# S14FullAmpV2.net
KiCad netlist of a schematic drawn in EAGLE
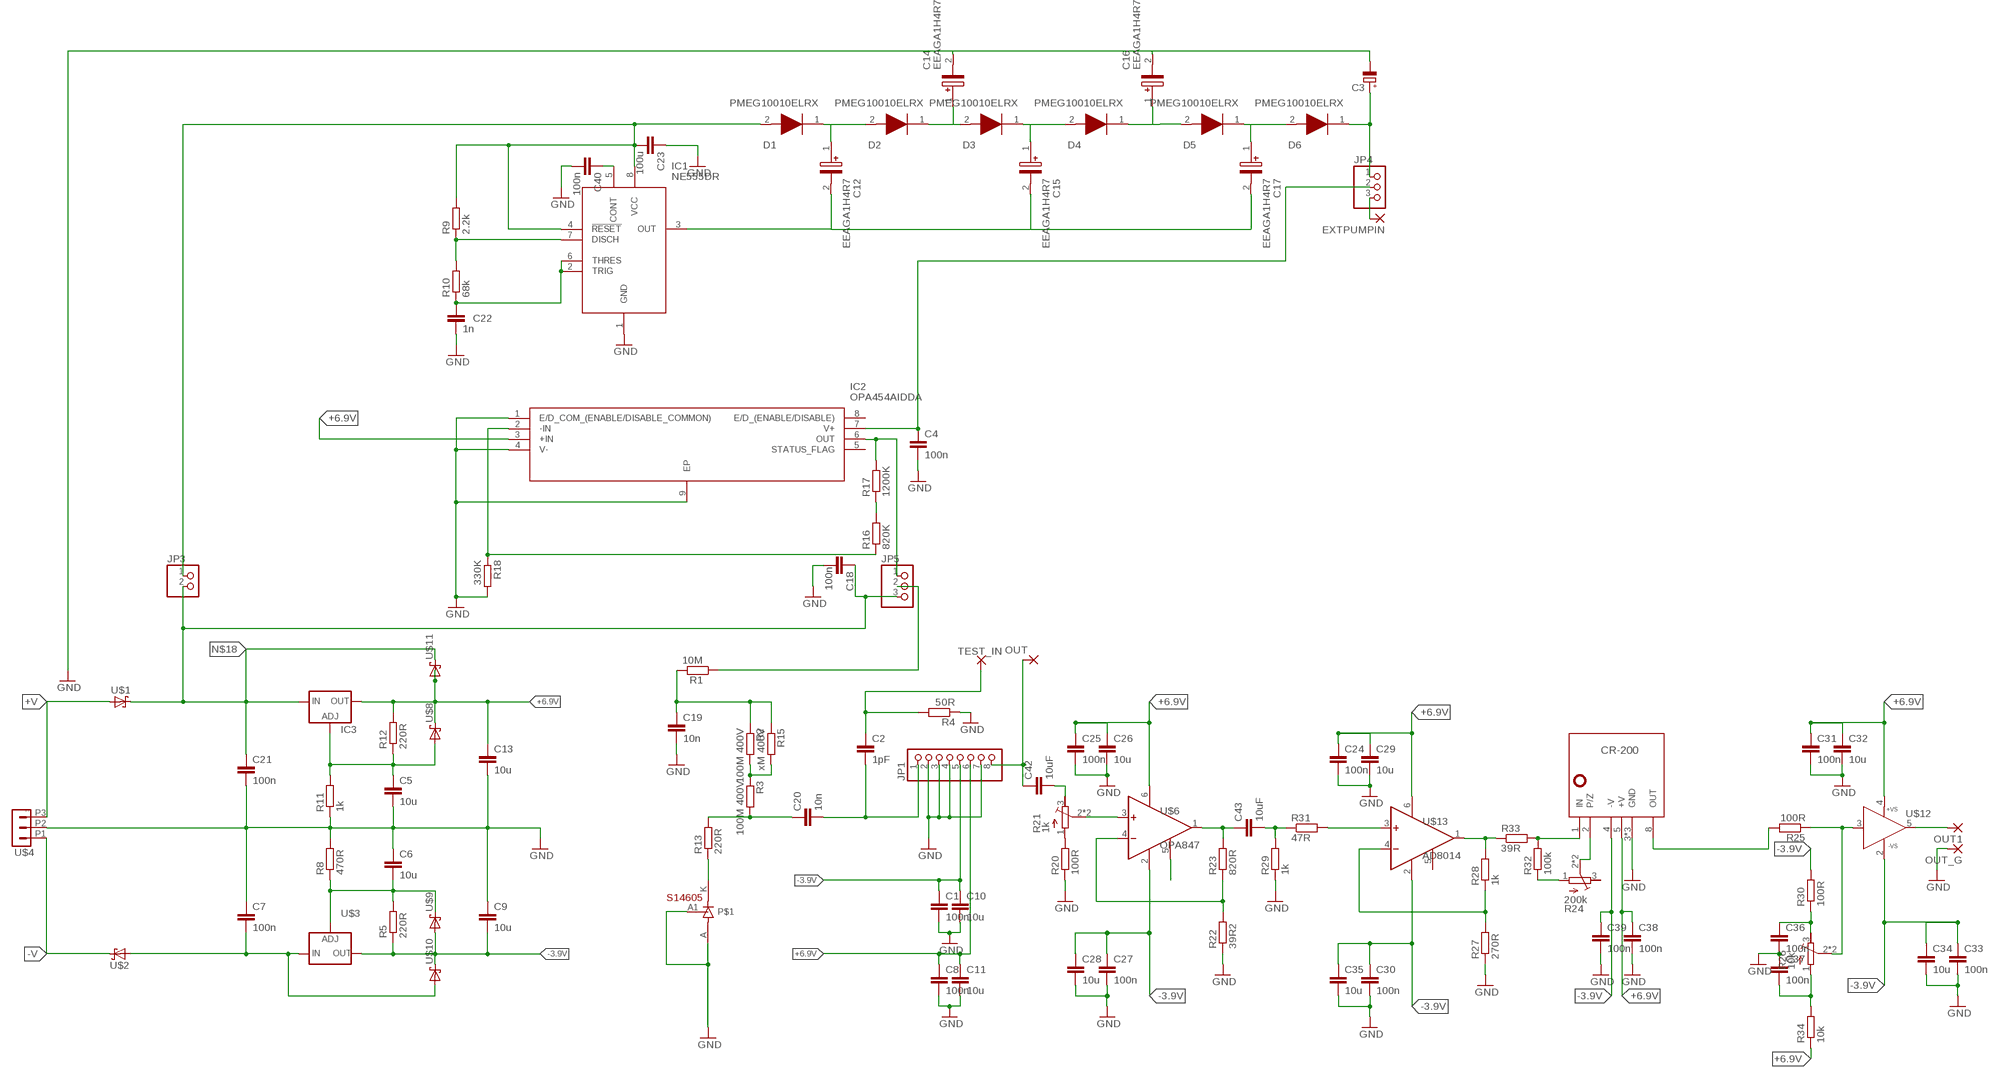
[diagram p0: schematic, sheet 1]

(export (version "E")
  (design (tool "Eeschema 10.0.6"))
  (components
    (comp (ref "C1")
      (value "100n")
      (footprint "eagle-import:C0603")
      (libsource (lib "eagle-import") (part "resistor_C-EUC0603"))
    )
    (comp (ref "C2")
      (value "1pF")
      (footprint "eagle-import:C0603")
      (libsource (lib "eagle-import") (part "C-EUC0603"))
    )
    (comp (ref "C3")
      (value "CPOL-EUE3.5-8")
      (footprint "eagle-import:E3,5-8")
      (libsource (lib "eagle-import") (part "CPOL-EUE3.5-8"))
    )
    (comp (ref "C4")
      (value "100n")
      (footprint "eagle-import:C0603")
      (libsource (lib "eagle-import") (part "resistor_C-EUC0603"))
    )
    (comp (ref "C5")
      (value "10u")
      (footprint "eagle-import:C0805")
      (libsource (lib "eagle-import") (part "C-EUC0805"))
    )
    (comp (ref "C6")
      (value "10u")
      (footprint "eagle-import:C0805")
      (libsource (lib "eagle-import") (part "C-EUC0805"))
    )
    (comp (ref "C7")
      (value "100n")
      (footprint "eagle-import:C0603")
      (libsource (lib "eagle-import") (part "C-EUC0603"))
    )
    (comp (ref "C8")
      (value "100n")
      (footprint "eagle-import:C0603")
      (libsource (lib "eagle-import") (part "resistor_C-EUC0603"))
    )
    (comp (ref "C9")
      (value "10u")
      (footprint "eagle-import:C0805")
      (libsource (lib "eagle-import") (part "C-EUC0805"))
    )
    (comp (ref "C10")
      (value "10u")
      (footprint "eagle-import:C0805")
      (libsource (lib "eagle-import") (part "resistor_C-EUC0805"))
    )
    (comp (ref "C11")
      (value "10u")
      (footprint "eagle-import:C0805")
      (libsource (lib "eagle-import") (part "resistor_C-EUC0805"))
    )
    (comp (ref "C12")
      (value "EEAGA1H4R7")
      (footprint "eagle-import:CAPPRD150W50D400H800")
      (libsource (lib "eagle-import") (part "EEAGA1H4R7"))
    )
    (comp (ref "C13")
      (value "10u")
      (footprint "eagle-import:C0805")
      (libsource (lib "eagle-import") (part "C-EUC0805"))
    )
    (comp (ref "C14")
      (value "EEAGA1H4R7")
      (footprint "eagle-import:CAPPRD150W50D400H800")
      (libsource (lib "eagle-import") (part "EEAGA1H4R7"))
    )
    (comp (ref "C15")
      (value "EEAGA1H4R7")
      (footprint "eagle-import:CAPPRD150W50D400H800")
      (libsource (lib "eagle-import") (part "EEAGA1H4R7"))
    )
    (comp (ref "C16")
      (value "EEAGA1H4R7")
      (footprint "eagle-import:CAPPRD150W50D400H800")
      (libsource (lib "eagle-import") (part "EEAGA1H4R7"))
    )
    (comp (ref "C17")
      (value "EEAGA1H4R7")
      (footprint "eagle-import:CAPPRD150W50D400H800")
      (libsource (lib "eagle-import") (part "EEAGA1H4R7"))
    )
    (comp (ref "C18")
      (value "100n")
      (footprint "eagle-import:C0603")
      (libsource (lib "eagle-import") (part "C-EUC0603"))
    )
    (comp (ref "C19")
      (value "10n")
      (footprint "eagle-import:C0603")
      (libsource (lib "eagle-import") (part "resistor_C-EUC0603"))
    )
    (comp (ref "C20")
      (value "10n")
      (footprint "eagle-import:C0603")
      (libsource (lib "eagle-import") (part "resistor_C-EUC0603"))
    )
    (comp (ref "C21")
      (value "100n")
      (footprint "eagle-import:C0603")
      (libsource (lib "eagle-import") (part "C-EUC0603"))
    )
    (comp (ref "C22")
      (value "1n")
      (footprint "eagle-import:C0603")
      (libsource (lib "eagle-import") (part "resistor_C-EUC0603"))
    )
    (comp (ref "C23")
      (value "100u")
      (footprint "eagle-import:C0603")
      (libsource (lib "eagle-import") (part "C-EUC0603"))
    )
    (comp (ref "C24")
      (value "100n")
      (footprint "eagle-import:C0603")
      (libsource (lib "eagle-import") (part "C-EUC0603"))
    )
    (comp (ref "C25")
      (value "100n")
      (footprint "eagle-import:C0603")
      (libsource (lib "eagle-import") (part "C-EUC0603"))
    )
    (comp (ref "C26")
      (value "10u")
      (footprint "eagle-import:C0805")
      (libsource (lib "eagle-import") (part "resistor_C-EUC0805"))
    )
    (comp (ref "C27")
      (value "100n")
      (footprint "eagle-import:C0603")
      (libsource (lib "eagle-import") (part "C-EUC0603"))
    )
    (comp (ref "C28")
      (value "10u")
      (footprint "eagle-import:C0805")
      (libsource (lib "eagle-import") (part "resistor_C-EUC0805"))
    )
    (comp (ref "C29")
      (value "10u")
      (footprint "eagle-import:C0805")
      (libsource (lib "eagle-import") (part "resistor_C-EUC0805"))
    )
    (comp (ref "C30")
      (value "100n")
      (footprint "eagle-import:C0603")
      (libsource (lib "eagle-import") (part "C-EUC0603"))
    )
    (comp (ref "C31")
      (value "100n")
      (footprint "eagle-import:C0603")
      (libsource (lib "eagle-import") (part "C-EUC0603"))
    )
    (comp (ref "C32")
      (value "10u")
      (footprint "eagle-import:C0805")
      (libsource (lib "eagle-import") (part "resistor_C-EUC0805"))
    )
    (comp (ref "C33")
      (value "100n")
      (footprint "eagle-import:C0603")
      (libsource (lib "eagle-import") (part "C-EUC0603"))
    )
    (comp (ref "C34")
      (value "10u")
      (footprint "eagle-import:C0805")
      (libsource (lib "eagle-import") (part "resistor_C-EUC0805"))
    )
    (comp (ref "C35")
      (value "10u")
      (footprint "eagle-import:C0805")
      (libsource (lib "eagle-import") (part "resistor_C-EUC0805"))
    )
    (comp (ref "C36")
      (value "100n")
      (footprint "eagle-import:C0603")
      (libsource (lib "eagle-import") (part "C-EUC0603"))
    )
    (comp (ref "C37")
      (value "100n")
      (footprint "eagle-import:C0603")
      (libsource (lib "eagle-import") (part "C-EUC0603"))
    )
    (comp (ref "C38")
      (value "100n")
      (footprint "eagle-import:C0603")
      (libsource (lib "eagle-import") (part "C-EUC0603"))
    )
    (comp (ref "C39")
      (value "100n")
      (footprint "eagle-import:C0603")
      (libsource (lib "eagle-import") (part "C-EUC0603"))
    )
    (comp (ref "C40")
      (value "100n")
      (footprint "eagle-import:C0603")
      (libsource (lib "eagle-import") (part "C-EUC0603"))
    )
    (comp (ref "C42")
      (value "10uF")
      (footprint "eagle-import:C0805")
      (libsource (lib "eagle-import") (part "resistor_348_C-EUC0805"))
    )
    (comp (ref "C43")
      (value "10uF")
      (footprint "eagle-import:C0805")
      (libsource (lib "eagle-import") (part "resistor_348_C-EUC0805"))
    )
    (comp (ref "CR-200")
      (value "CR-200H")
      (footprint "eagle-import:CR-XXX-H")
      (libsource (lib "eagle-import") (part "CR-200H"))
    )
    (comp (ref "D1")
      (value "PMEG10010ELRX")
      (footprint "eagle-import:SODFL3517X110N")
      (fields (field (name "MOUSER_PART_NUMBER") "771-PMEG10010ELRX"))
      (libsource (lib "eagle-import") (part "PMEG10010ELRX"))
    )
    (comp (ref "D2")
      (value "PMEG10010ELRX")
      (footprint "eagle-import:SODFL3517X110N")
      (fields (field (name "MOUSER_PART_NUMBER") "771-PMEG10010ELRX"))
      (libsource (lib "eagle-import") (part "PMEG10010ELRX"))
    )
    (comp (ref "D3")
      (value "PMEG10010ELRX")
      (footprint "eagle-import:SODFL3517X110N")
      (fields (field (name "MOUSER_PART_NUMBER") "771-PMEG10010ELRX"))
      (libsource (lib "eagle-import") (part "PMEG10010ELRX"))
    )
    (comp (ref "D4")
      (value "PMEG10010ELRX")
      (footprint "eagle-import:SODFL3517X110N")
      (fields (field (name "MOUSER_PART_NUMBER") "771-PMEG10010ELRX"))
      (libsource (lib "eagle-import") (part "PMEG10010ELRX"))
    )
    (comp (ref "D5")
      (value "PMEG10010ELRX")
      (footprint "eagle-import:SODFL3517X110N")
      (fields (field (name "MOUSER_PART_NUMBER") "771-PMEG10010ELRX"))
      (libsource (lib "eagle-import") (part "PMEG10010ELRX"))
    )
    (comp (ref "D6")
      (value "PMEG10010ELRX")
      (footprint "eagle-import:SODFL3517X110N")
      (fields (field (name "MOUSER_PART_NUMBER") "771-PMEG10010ELRX"))
      (libsource (lib "eagle-import") (part "PMEG10010ELRX"))
    )
    (comp (ref "EXTPUMPIN")
      (value "1,6/0,9")
      (footprint "eagle-import:1,6_0,9")
      (libsource (lib "eagle-import") (part "1,6/0,9"))
    )
    (comp (ref "IC1")
      (value "NE555DR")
      (footprint "eagle-import:SOIC127P600X175-8N")
      (libsource (lib "eagle-import") (part "NE555DR"))
    )
    (comp (ref "IC2")
      (value "OPA454AIDDA")
      (footprint "eagle-import:SOIC127P600X170-9N")
      (libsource (lib "eagle-import") (part "OPA454AIDDA"))
    )
    (comp (ref "IC3")
      (value "LM317")
      (footprint "eagle-import:SO-08")
      (libsource (lib "eagle-import") (part "LM317?"))
    )
    (comp (ref "JP1")
      (value "HEADER-1X8ROUND")
      (footprint "eagle-import:1X08_ROUND")
      (libsource (lib "eagle-import") (part "HEADER-1X8ROUND"))
    )
    (comp (ref "JP3")
      (value "PINHD-1X2")
      (footprint "eagle-import:1X02")
      (libsource (lib "eagle-import") (part "PINHD-1X2"))
    )
    (comp (ref "JP4")
      (value "PINHD-1X3")
      (footprint "eagle-import:1X03")
      (libsource (lib "eagle-import") (part "PINHD-1X3"))
    )
    (comp (ref "JP5")
      (value "PINHD-1X3")
      (footprint "eagle-import:1X03")
      (libsource (lib "eagle-import") (part "PINHD-1X3"))
    )
    (comp (ref "OUT")
      (value "1,6/0,9")
      (footprint "eagle-import:1,6_0,9")
      (libsource (lib "eagle-import") (part "1,6/0,9"))
    )
    (comp (ref "OUT1")
      (value "2,54/0,9")
      (footprint "eagle-import:2,54_0,9")
      (libsource (lib "eagle-import") (part "2,54/0,9"))
    )
    (comp (ref "OUT_G")
      (value "2,54/0,9")
      (footprint "eagle-import:2,54_0,9")
      (libsource (lib "eagle-import") (part "2,54/0,9"))
    )
    (comp (ref "R1")
      (value "10M")
      (footprint "eagle-import:M0805")
      (libsource (lib "eagle-import") (part "R-EU_M0805"))
    )
    (comp (ref "R2")
      (value "100M 400V")
      (footprint "eagle-import:M1206")
      (libsource (lib "eagle-import") (part "resistor_R-EU_M1206"))
    )
    (comp (ref "R3")
      (value "100M 400V")
      (footprint "eagle-import:M1206")
      (libsource (lib "eagle-import") (part "resistor_R-EU_M1206"))
    )
    (comp (ref "R4")
      (value "50R")
      (footprint "eagle-import:R0805")
      (libsource (lib "eagle-import") (part "R-EU_R0805"))
    )
    (comp (ref "R5")
      (value "220R")
      (footprint "eagle-import:R0603")
      (libsource (lib "eagle-import") (part "R-EU_R0603"))
    )
    (comp (ref "R8")
      (value "470R")
      (footprint "eagle-import:R0603")
      (libsource (lib "eagle-import") (part "R-EU_R0603"))
    )
    (comp (ref "R9")
      (value "2.2k")
      (footprint "eagle-import:R0805")
      (libsource (lib "eagle-import") (part "R-EU_R0805"))
    )
    (comp (ref "R10")
      (value "68k")
      (footprint "eagle-import:R0805")
      (libsource (lib "eagle-import") (part "R-EU_R0805"))
    )
    (comp (ref "R11")
      (value "1k")
      (footprint "eagle-import:R0603")
      (libsource (lib "eagle-import") (part "R-EU_R0603"))
    )
    (comp (ref "R12")
      (value "220R")
      (footprint "eagle-import:R0603")
      (libsource (lib "eagle-import") (part "R-EU_R0603"))
    )
    (comp (ref "R13")
      (value "220R")
      (footprint "eagle-import:R0805")
      (libsource (lib "eagle-import") (part "R-EU_R0805"))
    )
    (comp (ref "R15")
      (value "xM 400V")
      (footprint "eagle-import:M1206")
      (libsource (lib "eagle-import") (part "resistor_R-EU_M1206"))
    )
    (comp (ref "R16")
      (value "820K")
      (footprint "eagle-import:R0805")
      (libsource (lib "eagle-import") (part "R-EU_R0805"))
    )
    (comp (ref "R17")
      (value "1200K")
      (footprint "eagle-import:R0805")
      (libsource (lib "eagle-import") (part "R-EU_R0805"))
    )
    (comp (ref "R18")
      (value "330K")
      (footprint "eagle-import:R0805")
      (libsource (lib "eagle-import") (part "R-EU_R0805"))
    )
    (comp (ref "R20")
      (value "100R")
      (footprint "eagle-import:R0603")
      (libsource (lib "eagle-import") (part "R-EU_R0603"))
    )
    (comp (ref "R21")
      (value "1k")
      (footprint "eagle-import:RTRIM3299W")
      (libsource (lib "eagle-import") (part "R-TRIMM3299WS_UNI"))
    )
    (comp (ref "R22")
      (value "39R2")
      (footprint "eagle-import:R0603")
      (libsource (lib "eagle-import") (part "R-EU_R0603"))
    )
    (comp (ref "R23")
      (value "820R")
      (footprint "eagle-import:R0603")
      (libsource (lib "eagle-import") (part "R-EU_R0603"))
    )
    (comp (ref "R24")
      (value "200k")
      (footprint "eagle-import:RTRIM3299W")
      (libsource (lib "eagle-import") (part "R-TRIMM3299WS_UNI"))
    )
    (comp (ref "R25")
      (value "100R")
      (footprint "eagle-import:R0603")
      (libsource (lib "eagle-import") (part "R-EU_R0603"))
    )
    (comp (ref "R26")
      (value "10k")
      (footprint "eagle-import:RTRIM3299W")
      (libsource (lib "eagle-import") (part "R-TRIMM3299WS_UNI"))
    )
    (comp (ref "R27")
      (value "270R")
      (footprint "eagle-import:R0603")
      (libsource (lib "eagle-import") (part "R-EU_R0603"))
    )
    (comp (ref "R28")
      (value "1k")
      (footprint "eagle-import:R0603")
      (libsource (lib "eagle-import") (part "R-EU_R0603"))
    )
    (comp (ref "R29")
      (value "1k")
      (footprint "eagle-import:R0603")
      (libsource (lib "eagle-import") (part "R-EU_R0603"))
    )
    (comp (ref "R30")
      (value "100R")
      (footprint "eagle-import:R0603")
      (libsource (lib "eagle-import") (part "R-EU_R0603"))
    )
    (comp (ref "R31")
      (value "47R")
      (footprint "eagle-import:R0603")
      (libsource (lib "eagle-import") (part "R-EU_R0603"))
    )
    (comp (ref "R32")
      (value "100k")
      (footprint "eagle-import:R0603")
      (libsource (lib "eagle-import") (part "R-EU_R0603"))
    )
    (comp (ref "R33")
      (value "39R")
      (footprint "eagle-import:R0603")
      (libsource (lib "eagle-import") (part "R-EU_R0603"))
    )
    (comp (ref "R34")
      (value "10k")
      (footprint "eagle-import:R0603")
      (libsource (lib "eagle-import") (part "R-EU_R0603"))
    )
    (comp (ref "S1")
      (value "S14605")
      (footprint "eagle-import:RHDR3W53P0X254_1X3_762X246X425")
      (libsource (lib "eagle-import") (part "S14605"))
    )
    (comp (ref "TEST_IN")
      (value "1,6/0,9")
      (footprint "eagle-import:1,6_0,9")
      (libsource (lib "eagle-import") (part "1,6/0,9"))
    )
    (comp (ref "U$1")
      (value "BAS383")
      (footprint "eagle-import:MICROMELF-R")
      (libsource (lib "eagle-import") (part "BAS383"))
    )
    (comp (ref "U$2")
      (value "BAS383")
      (footprint "eagle-import:MICROMELF-R")
      (libsource (lib "eagle-import") (part "BAS383"))
    )
    (comp (ref "U$3")
      (value "LM337-SO8")
      (footprint "eagle-import:SO8")
      (libsource (lib "eagle-import") (part "LM337-SO8"))
    )
    (comp (ref "U$4")
      (value "XHT03T")
      (footprint "eagle-import:XHT03")
      (libsource (lib "eagle-import") (part "XHT03T"))
    )
    (comp (ref "U$6")
      (value "OPA847")
      (footprint "eagle-import:SOT23-6")
      (libsource (lib "eagle-import") (part "OPA847"))
    )
    (comp (ref "U$8")
      (value "BAS383")
      (footprint "eagle-import:MICROMELF-R")
      (libsource (lib "eagle-import") (part "BAS383"))
    )
    (comp (ref "U$9")
      (value "BAS383")
      (footprint "eagle-import:MICROMELF-R")
      (libsource (lib "eagle-import") (part "BAS383"))
    )
    (comp (ref "U$10")
      (value "BAS383")
      (footprint "eagle-import:MICROMELF-R")
      (libsource (lib "eagle-import") (part "BAS383"))
    )
    (comp (ref "U$11")
      (value "BAS383")
      (footprint "eagle-import:MICROMELF-R")
      (libsource (lib "eagle-import") (part "BAS383"))
    )
    (comp (ref "U$12")
      (value "MAX4201")
      (footprint "eagle-import:SOT23-5")
      (libsource (lib "eagle-import") (part "MAX4201"))
    )
    (comp (ref "U$13")
      (value "AD8014")
      (footprint "eagle-import:SOT23-6")
      (libsource (lib "eagle-import") (part "OPA847"))
    )
  )
  (nets
    (net (code "1") (name "+6.9V") (class "Default")
      (node (ref "C11") (pin "1") (pinfunction "1_1") (pintype "passive"))
      (node (ref "C13") (pin "1") (pinfunction "1_1") (pintype "passive"))
      (node (ref "C24") (pin "1") (pinfunction "1_1") (pintype "passive"))
      (node (ref "C25") (pin "1") (pinfunction "1_1") (pintype "passive"))
      (node (ref "C26") (pin "1") (pinfunction "1_1") (pintype "passive"))
      (node (ref "C29") (pin "1") (pinfunction "1_1") (pintype "passive"))
      (node (ref "C31") (pin "1") (pinfunction "1_1") (pintype "passive"))
      (node (ref "C32") (pin "1") (pinfunction "1_1") (pintype "passive"))
      (node (ref "C38") (pin "1") (pinfunction "1_1") (pintype "passive"))
      (node (ref "C8") (pin "1") (pinfunction "1_1") (pintype "passive"))
      (node (ref "CR-200") (pin "5") (pinfunction "+V_5") (pintype "power_in"))
      (node (ref "IC2") (pin "3") (pinfunction "+IN_3") (pintype "bidirectional"))
      (node (ref "IC3") (pin "2") (pinfunction "OUT_2") (pintype "passive"))
      (node (ref "IC3") (pin "3") (pinfunction "OUT_3") (pintype "passive"))
      (node (ref "IC3") (pin "6") (pinfunction "OUT_6") (pintype "passive"))
      (node (ref "IC3") (pin "7") (pinfunction "OUT_7") (pintype "passive"))
      (node (ref "JP1") (pin "6") (pinfunction "6_6") (pintype "passive"))
      (node (ref "R12") (pin "2") (pinfunction "2_2") (pintype "passive"))
      (node (ref "R34") (pin "1") (pinfunction "1_1") (pintype "passive"))
      (node (ref "U$11") (pin "A") (pinfunction "A_A") (pintype "passive"))
      (node (ref "U$12") (pin "4") (pinfunction "+VS_4") (pintype "input"))
      (node (ref "U$13") (pin "6") (pinfunction "V+_6") (pintype "power_in"))
      (node (ref "U$6") (pin "6") (pinfunction "V+_6") (pintype "power_in"))
      (node (ref "U$8") (pin "C") (pinfunction "C_C") (pintype "passive"))
    )
    (net (code "2") (name "+V") (class "Default")
      (node (ref "U$1") (pin "A") (pinfunction "A_A") (pintype "passive"))
      (node (ref "U$4") (pin "P3") (pinfunction "3_P3") (pintype "passive"))
    )
    (net (code "3") (name "-3.9V") (class "Default")
      (node (ref "C1") (pin "1") (pinfunction "1_1") (pintype "passive"))
      (node (ref "C10") (pin "1") (pinfunction "1_1") (pintype "passive"))
      (node (ref "C27") (pin "1") (pinfunction "1_1") (pintype "passive"))
      (node (ref "C28") (pin "1") (pinfunction "1_1") (pintype "passive"))
      (node (ref "C30") (pin "1") (pinfunction "1_1") (pintype "passive"))
      (node (ref "C33") (pin "1") (pinfunction "1_1") (pintype "passive"))
      (node (ref "C34") (pin "1") (pinfunction "1_1") (pintype "passive"))
      (node (ref "C35") (pin "1") (pinfunction "1_1") (pintype "passive"))
      (node (ref "C39") (pin "1") (pinfunction "1_1") (pintype "passive"))
      (node (ref "C9") (pin "2") (pinfunction "2_2") (pintype "passive"))
      (node (ref "CR-200") (pin "4") (pinfunction "-V_4") (pintype "power_in"))
      (node (ref "JP1") (pin "5") (pinfunction "5_5") (pintype "passive"))
      (node (ref "R30") (pin "2") (pinfunction "2_2") (pintype "passive"))
      (node (ref "R5") (pin "1") (pinfunction "1_1") (pintype "passive"))
      (node (ref "U$10") (pin "C") (pinfunction "C_C") (pintype "passive"))
      (node (ref "U$12") (pin "2") (pinfunction "-VS_2") (pintype "input"))
      (node (ref "U$13") (pin "2") (pinfunction "V-_2") (pintype "power_in"))
      (node (ref "U$3") (pin "1") (pinfunction "OUT_1") (pintype "passive"))
      (node (ref "U$6") (pin "2") (pinfunction "V-_2") (pintype "power_in"))
      (node (ref "U$9") (pin "A") (pinfunction "A_A") (pintype "passive"))
    )
    (net (code "4") (name "-V") (class "Default")
      (node (ref "U$2") (pin "C") (pinfunction "C_C") (pintype "passive"))
      (node (ref "U$4") (pin "P1") (pinfunction "1_P1") (pintype "passive"))
    )
    (net (code "5") (name "/SH") (class "Default")
      (node (ref "U$13") (pin "5") (pinfunction "SH_5") (pintype "power_in"))
    )
    (net (code "6") (name "GND") (class "Default")
      (node (ref "C1") (pin "2") (pinfunction "2_2") (pintype "passive"))
      (node (ref "C10") (pin "2") (pinfunction "2_2") (pintype "passive"))
      (node (ref "C11") (pin "2") (pinfunction "2_2") (pintype "passive"))
      (node (ref "C13") (pin "2") (pinfunction "2_2") (pintype "passive"))
      (node (ref "C14") (pin "2") (pinfunction "-_2") (pintype "bidirectional"))
      (node (ref "C16") (pin "2") (pinfunction "-_2") (pintype "bidirectional"))
      (node (ref "C18") (pin "2") (pinfunction "2_2") (pintype "passive"))
      (node (ref "C19") (pin "2") (pinfunction "2_2") (pintype "passive"))
      (node (ref "C21") (pin "2") (pinfunction "2_2") (pintype "passive"))
      (node (ref "C22") (pin "2") (pinfunction "2_2") (pintype "passive"))
      (node (ref "C23") (pin "1") (pinfunction "1_1") (pintype "passive"))
      (node (ref "C24") (pin "2") (pinfunction "2_2") (pintype "passive"))
      (node (ref "C25") (pin "2") (pinfunction "2_2") (pintype "passive"))
      (node (ref "C26") (pin "2") (pinfunction "2_2") (pintype "passive"))
      (node (ref "C27") (pin "2") (pinfunction "2_2") (pintype "passive"))
      (node (ref "C28") (pin "2") (pinfunction "2_2") (pintype "passive"))
      (node (ref "C29") (pin "2") (pinfunction "2_2") (pintype "passive"))
      (node (ref "C3") (pin "-") (pinfunction "-_-") (pintype "passive"))
      (node (ref "C30") (pin "2") (pinfunction "2_2") (pintype "passive"))
      (node (ref "C31") (pin "2") (pinfunction "2_2") (pintype "passive"))
      (node (ref "C32") (pin "2") (pinfunction "2_2") (pintype "passive"))
      (node (ref "C33") (pin "2") (pinfunction "2_2") (pintype "passive"))
      (node (ref "C34") (pin "2") (pinfunction "2_2") (pintype "passive"))
      (node (ref "C35") (pin "2") (pinfunction "2_2") (pintype "passive"))
      (node (ref "C36") (pin "2") (pinfunction "2_2") (pintype "passive"))
      (node (ref "C37") (pin "1") (pinfunction "1_1") (pintype "passive"))
      (node (ref "C38") (pin "2") (pinfunction "2_2") (pintype "passive"))
      (node (ref "C39") (pin "2") (pinfunction "2_2") (pintype "passive"))
      (node (ref "C4") (pin "2") (pinfunction "2_2") (pintype "passive"))
      (node (ref "C40") (pin "2") (pinfunction "2_2") (pintype "passive"))
      (node (ref "C5") (pin "2") (pinfunction "2_2") (pintype "passive"))
      (node (ref "C6") (pin "1") (pinfunction "1_1") (pintype "passive"))
      (node (ref "C7") (pin "1") (pinfunction "1_1") (pintype "passive"))
      (node (ref "C8") (pin "2") (pinfunction "2_2") (pintype "passive"))
      (node (ref "C9") (pin "1") (pinfunction "1_1") (pintype "passive"))
      (node (ref "CR-200") (pin "3") (pinfunction "GND_3") (pintype "power_in"))
      (node (ref "CR-200") (pin "6") (pinfunction "GND_6") (pintype "power_in"))
      (node (ref "CR-200") (pin "7") (pinfunction "GND_7") (pintype "power_in"))
      (node (ref "IC1") (pin "1") (pinfunction "GND_1") (pintype "bidirectional"))
      (node (ref "IC2") (pin "1") (pinfunction "E/D_COM_(ENABLE/DISABLE_COMMON)_1") (pintype "bidirectional"))
      (node (ref "IC2") (pin "4") (pinfunction "V-_4") (pintype "bidirectional"))
      (node (ref "IC2") (pin "9") (pinfunction "EP_9") (pintype "bidirectional"))
      (node (ref "JP1") (pin "2") (pinfunction "2_2") (pintype "passive"))
      (node (ref "JP1") (pin "3") (pinfunction "3_3") (pintype "passive"))
      (node (ref "JP1") (pin "4") (pinfunction "4_4") (pintype "passive"))
      (node (ref "JP1") (pin "7") (pinfunction "7_7") (pintype "passive"))
      (node (ref "OUT_G") (pin "1") (pinfunction "P_1") (pintype "passive"))
      (node (ref "R11") (pin "1") (pinfunction "1_1") (pintype "passive"))
      (node (ref "R18") (pin "2") (pinfunction "2_2") (pintype "passive"))
      (node (ref "R20") (pin "1") (pinfunction "1_1") (pintype "passive"))
      (node (ref "R22") (pin "1") (pinfunction "1_1") (pintype "passive"))
      (node (ref "R27") (pin "1") (pinfunction "1_1") (pintype "passive"))
      (node (ref "R29") (pin "1") (pinfunction "1_1") (pintype "passive"))
      (node (ref "R4") (pin "1") (pinfunction "1_1") (pintype "passive"))
      (node (ref "R8") (pin "2") (pinfunction "2_2") (pintype "passive"))
      (node (ref "S1") (pin "A") (pinfunction "ANODE_A") (pintype "bidirectional"))
      (node (ref "S1") (pin "A1") (pinfunction "P$1_A1") (pintype "bidirectional"))
      (node (ref "U$4") (pin "P2") (pinfunction "2_P2") (pintype "passive"))
    )
    (net (code "7") (name "N$18") (class "Default")
      (node (ref "C18") (pin "1") (pinfunction "1_1") (pintype "passive"))
      (node (ref "C21") (pin "1") (pinfunction "1_1") (pintype "passive"))
      (node (ref "IC3") (pin "1") (pinfunction "IN_1") (pintype "input"))
      (node (ref "JP3") (pin "2") (pinfunction "2_2") (pintype "passive"))
      (node (ref "JP5") (pin "3") (pinfunction "3_3") (pintype "passive"))
      (node (ref "U$1") (pin "C") (pinfunction "C_C") (pintype "passive"))
      (node (ref "U$11") (pin "C") (pinfunction "C_C") (pintype "passive"))
    )
    (net (code "8") (name "Net-(C2-Pad2)") (class "Default")
      (node (ref "C2") (pin "2") (pinfunction "2_2") (pintype "passive"))
      (node (ref "C20") (pin "2") (pinfunction "2_2") (pintype "passive"))
      (node (ref "JP1") (pin "1") (pinfunction "1_1") (pintype "passive"))
    )
    (net (code "9") (name "Net-(C7-Pad2)") (class "Default")
      (node (ref "C7") (pin "2") (pinfunction "2_2") (pintype "passive"))
      (node (ref "U$10") (pin "A") (pinfunction "A_A") (pintype "passive"))
      (node (ref "U$2") (pin "A") (pinfunction "A_A") (pintype "passive"))
      (node (ref "U$3") (pin "2") (pinfunction "IN_2") (pintype "input"))
      (node (ref "U$3") (pin "3") (pinfunction "IN_3") (pintype "input"))
      (node (ref "U$3") (pin "6") (pinfunction "IN_6") (pintype "input"))
      (node (ref "U$3") (pin "7") (pinfunction "IN_7") (pintype "input"))
    )
    (net (code "10") (name "Net-(C12-+)") (class "Default")
      (node (ref "C12") (pin "1") (pinfunction "+_1") (pintype "bidirectional"))
      (node (ref "D1") (pin "1") (pinfunction "K_1") (pintype "bidirectional"))
      (node (ref "D2") (pin "2") (pinfunction "A_2") (pintype "bidirectional"))
    )
    (net (code "11") (name "Net-(C12--)") (class "Default")
      (node (ref "C12") (pin "2") (pinfunction "-_2") (pintype "bidirectional"))
      (node (ref "C15") (pin "2") (pinfunction "-_2") (pintype "bidirectional"))
      (node (ref "C17") (pin "2") (pinfunction "-_2") (pintype "bidirectional"))
      (node (ref "IC1") (pin "3") (pinfunction "OUT_3") (pintype "bidirectional"))
    )
    (net (code "12") (name "Net-(C14-+)") (class "Default")
      (node (ref "C14") (pin "1") (pinfunction "+_1") (pintype "bidirectional"))
      (node (ref "D2") (pin "1") (pinfunction "K_1") (pintype "bidirectional"))
      (node (ref "D3") (pin "2") (pinfunction "A_2") (pintype "bidirectional"))
    )
    (net (code "13") (name "Net-(C15-+)") (class "Default")
      (node (ref "C15") (pin "1") (pinfunction "+_1") (pintype "bidirectional"))
      (node (ref "D3") (pin "1") (pinfunction "K_1") (pintype "bidirectional"))
      (node (ref "D4") (pin "2") (pinfunction "A_2") (pintype "bidirectional"))
    )
    (net (code "14") (name "Net-(C16-+)") (class "Default")
      (node (ref "C16") (pin "1") (pinfunction "+_1") (pintype "bidirectional"))
      (node (ref "D4") (pin "1") (pinfunction "K_1") (pintype "bidirectional"))
      (node (ref "D5") (pin "2") (pinfunction "A_2") (pintype "bidirectional"))
    )
    (net (code "15") (name "Net-(C17-+)") (class "Default")
      (node (ref "C17") (pin "1") (pinfunction "+_1") (pintype "bidirectional"))
      (node (ref "D5") (pin "1") (pinfunction "K_1") (pintype "bidirectional"))
      (node (ref "D6") (pin "2") (pinfunction "A_2") (pintype "bidirectional"))
    )
    (net (code "16") (name "Net-(C19-Pad1)") (class "Default")
      (node (ref "C19") (pin "1") (pinfunction "1_1") (pintype "passive"))
      (node (ref "R1") (pin "2") (pinfunction "2_2") (pintype "passive"))
      (node (ref "R15") (pin "1") (pinfunction "1_1") (pintype "passive"))
      (node (ref "R2") (pin "1") (pinfunction "1_1") (pintype "passive"))
    )
    (net (code "17") (name "Net-(C20-Pad1)") (class "Default")
      (node (ref "C20") (pin "1") (pinfunction "1_1") (pintype "passive"))
      (node (ref "R13") (pin "2") (pinfunction "2_2") (pintype "passive"))
      (node (ref "R3") (pin "2") (pinfunction "2_2") (pintype "passive"))
    )
    (net (code "18") (name "Net-(C43-Pad2)") (class "Default")
      (node (ref "C43") (pin "2") (pinfunction "2_2") (pintype "passive"))
      (node (ref "R29") (pin "2") (pinfunction "2_2") (pintype "passive"))
      (node (ref "R31") (pin "1") (pinfunction "1_1") (pintype "passive"))
    )
    (net (code "19") (name "Net-(CR-200-IN)") (class "Default")
      (node (ref "CR-200") (pin "1") (pinfunction "IN_1") (pintype "input"))
      (node (ref "R32") (pin "2") (pinfunction "2_2") (pintype "passive"))
      (node (ref "R33") (pin "2") (pinfunction "2_2") (pintype "passive"))
    )
    (net (code "20") (name "Net-(CR-200-OUT)") (class "Default")
      (node (ref "CR-200") (pin "8") (pinfunction "OUT_8") (pintype "output"))
      (node (ref "R25") (pin "2") (pinfunction "2_2") (pintype "passive"))
    )
    (net (code "21") (name "Net-(CR-200-P{slash}Z)") (class "Default")
      (node (ref "CR-200") (pin "2") (pinfunction "P/Z_2") (pintype "bidirectional"))
      (node (ref "R24") (pin "2") (pinfunction "S_2") (pintype "passive"))
      (node (ref "R24") (pin "4") (pinfunction "S_4") (pintype "passive"))
    )
    (net (code "22") (name "Net-(D1-A)") (class "Default")
      (node (ref "C23") (pin "2") (pinfunction "2_2") (pintype "passive"))
      (node (ref "D1") (pin "2") (pinfunction "A_2") (pintype "bidirectional"))
      (node (ref "IC1") (pin "4") (pinfunction "~{RESET}_4") (pintype "bidirectional"))
      (node (ref "IC1") (pin "8") (pinfunction "VCC_8") (pintype "bidirectional"))
      (node (ref "JP3") (pin "1") (pinfunction "1_1") (pintype "passive"))
      (node (ref "R9") (pin "2") (pinfunction "2_2") (pintype "passive"))
    )
    (net (code "23") (name "Net-(D6-K)") (class "Default")
      (node (ref "C3") (pin "+") (pinfunction "+_+") (pintype "passive"))
      (node (ref "D6") (pin "1") (pinfunction "K_1") (pintype "bidirectional"))
      (node (ref "JP4") (pin "1") (pinfunction "1_1") (pintype "passive"))
    )
    (net (code "24") (name "Net-(EXTPUMPIN-P)") (class "Default")
      (node (ref "EXTPUMPIN") (pin "1") (pinfunction "P_1") (pintype "passive"))
      (node (ref "JP4") (pin "3") (pinfunction "3_3") (pintype "passive"))
    )
    (net (code "25") (name "Net-(IC1-CONT)") (class "Default")
      (node (ref "C40") (pin "1") (pinfunction "1_1") (pintype "passive"))
      (node (ref "IC1") (pin "5") (pinfunction "CONT_5") (pintype "bidirectional"))
    )
    (net (code "26") (name "Net-(IC1-DISCH)") (class "Default")
      (node (ref "IC1") (pin "7") (pinfunction "DISCH_7") (pintype "bidirectional"))
      (node (ref "R10") (pin "2") (pinfunction "2_2") (pintype "passive"))
      (node (ref "R9") (pin "1") (pinfunction "1_1") (pintype "passive"))
    )
    (net (code "27") (name "Net-(IC1-THRES)") (class "Default")
      (node (ref "C22") (pin "1") (pinfunction "1_1") (pintype "passive"))
      (node (ref "IC1") (pin "2") (pinfunction "TRIG_2") (pintype "bidirectional"))
      (node (ref "IC1") (pin "6") (pinfunction "THRES_6") (pintype "bidirectional"))
      (node (ref "R10") (pin "1") (pinfunction "1_1") (pintype "passive"))
    )
    (net (code "28") (name "Net-(IC2--IN)") (class "Default")
      (node (ref "IC2") (pin "2") (pinfunction "-IN_2") (pintype "bidirectional"))
      (node (ref "R16") (pin "1") (pinfunction "1_1") (pintype "passive"))
      (node (ref "R18") (pin "1") (pinfunction "1_1") (pintype "passive"))
    )
    (net (code "29") (name "Net-(IC2-OUT)") (class "Default")
      (node (ref "IC2") (pin "6") (pinfunction "OUT_6") (pintype "bidirectional"))
      (node (ref "JP5") (pin "1") (pinfunction "1_1") (pintype "passive"))
      (node (ref "R17") (pin "2") (pinfunction "2_2") (pintype "passive"))
    )
    (net (code "30") (name "Net-(IC2-V+)") (class "Default")
      (node (ref "C4") (pin "1") (pinfunction "1_1") (pintype "passive"))
      (node (ref "IC2") (pin "7") (pinfunction "V+_7") (pintype "bidirectional"))
      (node (ref "JP4") (pin "2") (pinfunction "2_2") (pintype "passive"))
    )
    (net (code "31") (name "Net-(IC3-ADJ)") (class "Default")
      (node (ref "C5") (pin "1") (pinfunction "1_1") (pintype "passive"))
      (node (ref "IC3") (pin "4") (pinfunction "ADJ_4") (pintype "input"))
      (node (ref "R11") (pin "2") (pinfunction "2_2") (pintype "passive"))
      (node (ref "R12") (pin "1") (pinfunction "1_1") (pintype "passive"))
      (node (ref "U$8") (pin "A") (pinfunction "A_A") (pintype "passive"))
    )
    (net (code "32") (name "Net-(JP5-Pad2)") (class "Default")
      (node (ref "JP5") (pin "2") (pinfunction "2_2") (pintype "passive"))
      (node (ref "R1") (pin "1") (pinfunction "1_1") (pintype "passive"))
    )
    (net (code "33") (name "Net-(OUT-P)") (class "Default")
      (node (ref "C42") (pin "1") (pinfunction "1_1") (pintype "passive"))
      (node (ref "JP1") (pin "8") (pinfunction "8_8") (pintype "passive"))
      (node (ref "OUT") (pin "1") (pinfunction "P_1") (pintype "passive"))
    )
    (net (code "34") (name "Net-(OUT1-P)") (class "Default")
      (node (ref "OUT1") (pin "1") (pinfunction "P_1") (pintype "passive"))
      (node (ref "U$12") (pin "5") (pinfunction "OUT_5") (pintype "output"))
    )
    (net (code "35") (name "Net-(R15-Pad2)") (class "Default")
      (node (ref "R15") (pin "2") (pinfunction "2_2") (pintype "passive"))
      (node (ref "R2") (pin "2") (pinfunction "2_2") (pintype "passive"))
      (node (ref "R3") (pin "1") (pinfunction "1_1") (pintype "passive"))
    )
    (net (code "36") (name "Net-(R16-Pad2)") (class "Default")
      (node (ref "R16") (pin "2") (pinfunction "2_2") (pintype "passive"))
      (node (ref "R17") (pin "1") (pinfunction "1_1") (pintype "passive"))
    )
    (net (code "37") (name "Net-(R21-A)") (class "Default")
      (node (ref "R20") (pin "2") (pinfunction "2_2") (pintype "passive"))
      (node (ref "R21") (pin "1") (pinfunction "A_1") (pintype "passive"))
    )
    (net (code "38") (name "Net-(R21-E)") (class "Default")
      (node (ref "C42") (pin "2") (pinfunction "2_2") (pintype "passive"))
      (node (ref "R21") (pin "3") (pinfunction "E_3") (pintype "passive"))
    )
    (net (code "39") (name "Net-(R24-A)") (class "Default")
      (node (ref "R24") (pin "1") (pinfunction "A_1") (pintype "passive"))
      (node (ref "R32") (pin "1") (pinfunction "1_1") (pintype "passive"))
    )
    (net (code "40") (name "Net-(R26-A)") (class "Default")
      (node (ref "C37") (pin "2") (pinfunction "2_2") (pintype "passive"))
      (node (ref "R26") (pin "1") (pinfunction "A_1") (pintype "passive"))
      (node (ref "R34") (pin "2") (pinfunction "2_2") (pintype "passive"))
    )
    (net (code "41") (name "Net-(R26-E)") (class "Default")
      (node (ref "C36") (pin "1") (pinfunction "1_1") (pintype "passive"))
      (node (ref "R26") (pin "3") (pinfunction "E_3") (pintype "passive"))
      (node (ref "R30") (pin "1") (pinfunction "1_1") (pintype "passive"))
    )
    (net (code "42") (name "Net-(S1-KATHODE)") (class "Default")
      (node (ref "R13") (pin "1") (pinfunction "1_1") (pintype "passive"))
      (node (ref "S1") (pin "K") (pinfunction "KATHODE_K") (pintype "bidirectional"))
    )
    (net (code "43") (name "Net-(TEST_IN-P)") (class "Default")
      (node (ref "C2") (pin "1") (pinfunction "1_1") (pintype "passive"))
      (node (ref "R4") (pin "2") (pinfunction "2_2") (pintype "passive"))
      (node (ref "TEST_IN") (pin "1") (pinfunction "P_1") (pintype "passive"))
    )
    (net (code "44") (name "Net-(U$3-ADJ)") (class "Default")
      (node (ref "C6") (pin "2") (pinfunction "2_2") (pintype "passive"))
      (node (ref "R5") (pin "2") (pinfunction "2_2") (pintype "passive"))
      (node (ref "R8") (pin "1") (pinfunction "1_1") (pintype "passive"))
      (node (ref "U$3") (pin "4") (pinfunction "ADJ_4") (pintype "input"))
      (node (ref "U$9") (pin "C") (pinfunction "C_C") (pintype "passive"))
    )
    (net (code "45") (name "Net-(U$6-+IN)") (class "Default")
      (node (ref "R21") (pin "2") (pinfunction "S_2") (pintype "passive"))
      (node (ref "R21") (pin "4") (pinfunction "S_4") (pintype "passive"))
      (node (ref "U$6") (pin "3") (pinfunction "+IN_3") (pintype "input"))
    )
    (net (code "46") (name "Net-(U$6--IN)") (class "Default")
      (node (ref "R22") (pin "2") (pinfunction "2_2") (pintype "passive"))
      (node (ref "R23") (pin "1") (pinfunction "1_1") (pintype "passive"))
      (node (ref "U$6") (pin "4") (pinfunction "-IN_4") (pintype "input"))
    )
    (net (code "47") (name "Net-(U$6-OUT)") (class "Default")
      (node (ref "C43") (pin "1") (pinfunction "1_1") (pintype "passive"))
      (node (ref "R23") (pin "2") (pinfunction "2_2") (pintype "passive"))
      (node (ref "U$6") (pin "1") (pinfunction "OUT_1") (pintype "output"))
    )
    (net (code "48") (name "Net-(U$12-IN)") (class "Default")
      (node (ref "R25") (pin "1") (pinfunction "1_1") (pintype "passive"))
      (node (ref "R26") (pin "2") (pinfunction "S_2") (pintype "passive"))
      (node (ref "R26") (pin "4") (pinfunction "S_4") (pintype "passive"))
      (node (ref "U$12") (pin "3") (pinfunction "IN_3") (pintype "input"))
    )
    (net (code "49") (name "Net-(U$13-+IN)") (class "Default")
      (node (ref "R31") (pin "2") (pinfunction "2_2") (pintype "passive"))
      (node (ref "U$13") (pin "3") (pinfunction "+IN_3") (pintype "input"))
    )
    (net (code "50") (name "Net-(U$13--IN)") (class "Default")
      (node (ref "R27") (pin "2") (pinfunction "2_2") (pintype "passive"))
      (node (ref "R28") (pin "1") (pinfunction "1_1") (pintype "passive"))
      (node (ref "U$13") (pin "4") (pinfunction "-IN_4") (pintype "input"))
    )
    (net (code "51") (name "Net-(U$13-OUT)") (class "Default")
      (node (ref "R28") (pin "2") (pinfunction "2_2") (pintype "passive"))
      (node (ref "R33") (pin "1") (pinfunction "1_1") (pintype "passive"))
      (node (ref "U$13") (pin "1") (pinfunction "OUT_1") (pintype "output"))
    )
    (net (code "52") (name "unconnected-(IC2-E{slash}D_(ENABLE{slash}DISABLE)-Pad8)") (class "Default")
      (node (ref "IC2") (pin "8") (pinfunction "E/D_(ENABLE/DISABLE)_8") (pintype "bidirectional"))
    )
    (net (code "53") (name "unconnected-(IC2-STATUS_FLAG-Pad5)") (class "Default")
      (node (ref "IC2") (pin "5") (pinfunction "STATUS_FLAG_5") (pintype "bidirectional"))
    )
    (net (code "54") (name "unconnected-(R24-E-Pad3)") (class "Default")
      (node (ref "R24") (pin "3") (pinfunction "E_3") (pintype "passive"))
    )
    (net (code "55") (name "unconnected-(U$6-SH-Pad5)") (class "Default")
      (node (ref "U$6") (pin "5") (pinfunction "SH_5") (pintype "power_in"))
    )
  )
)
